# OTEStamperLED.net
KiCad netlist of a schematic drawn in EAGLE
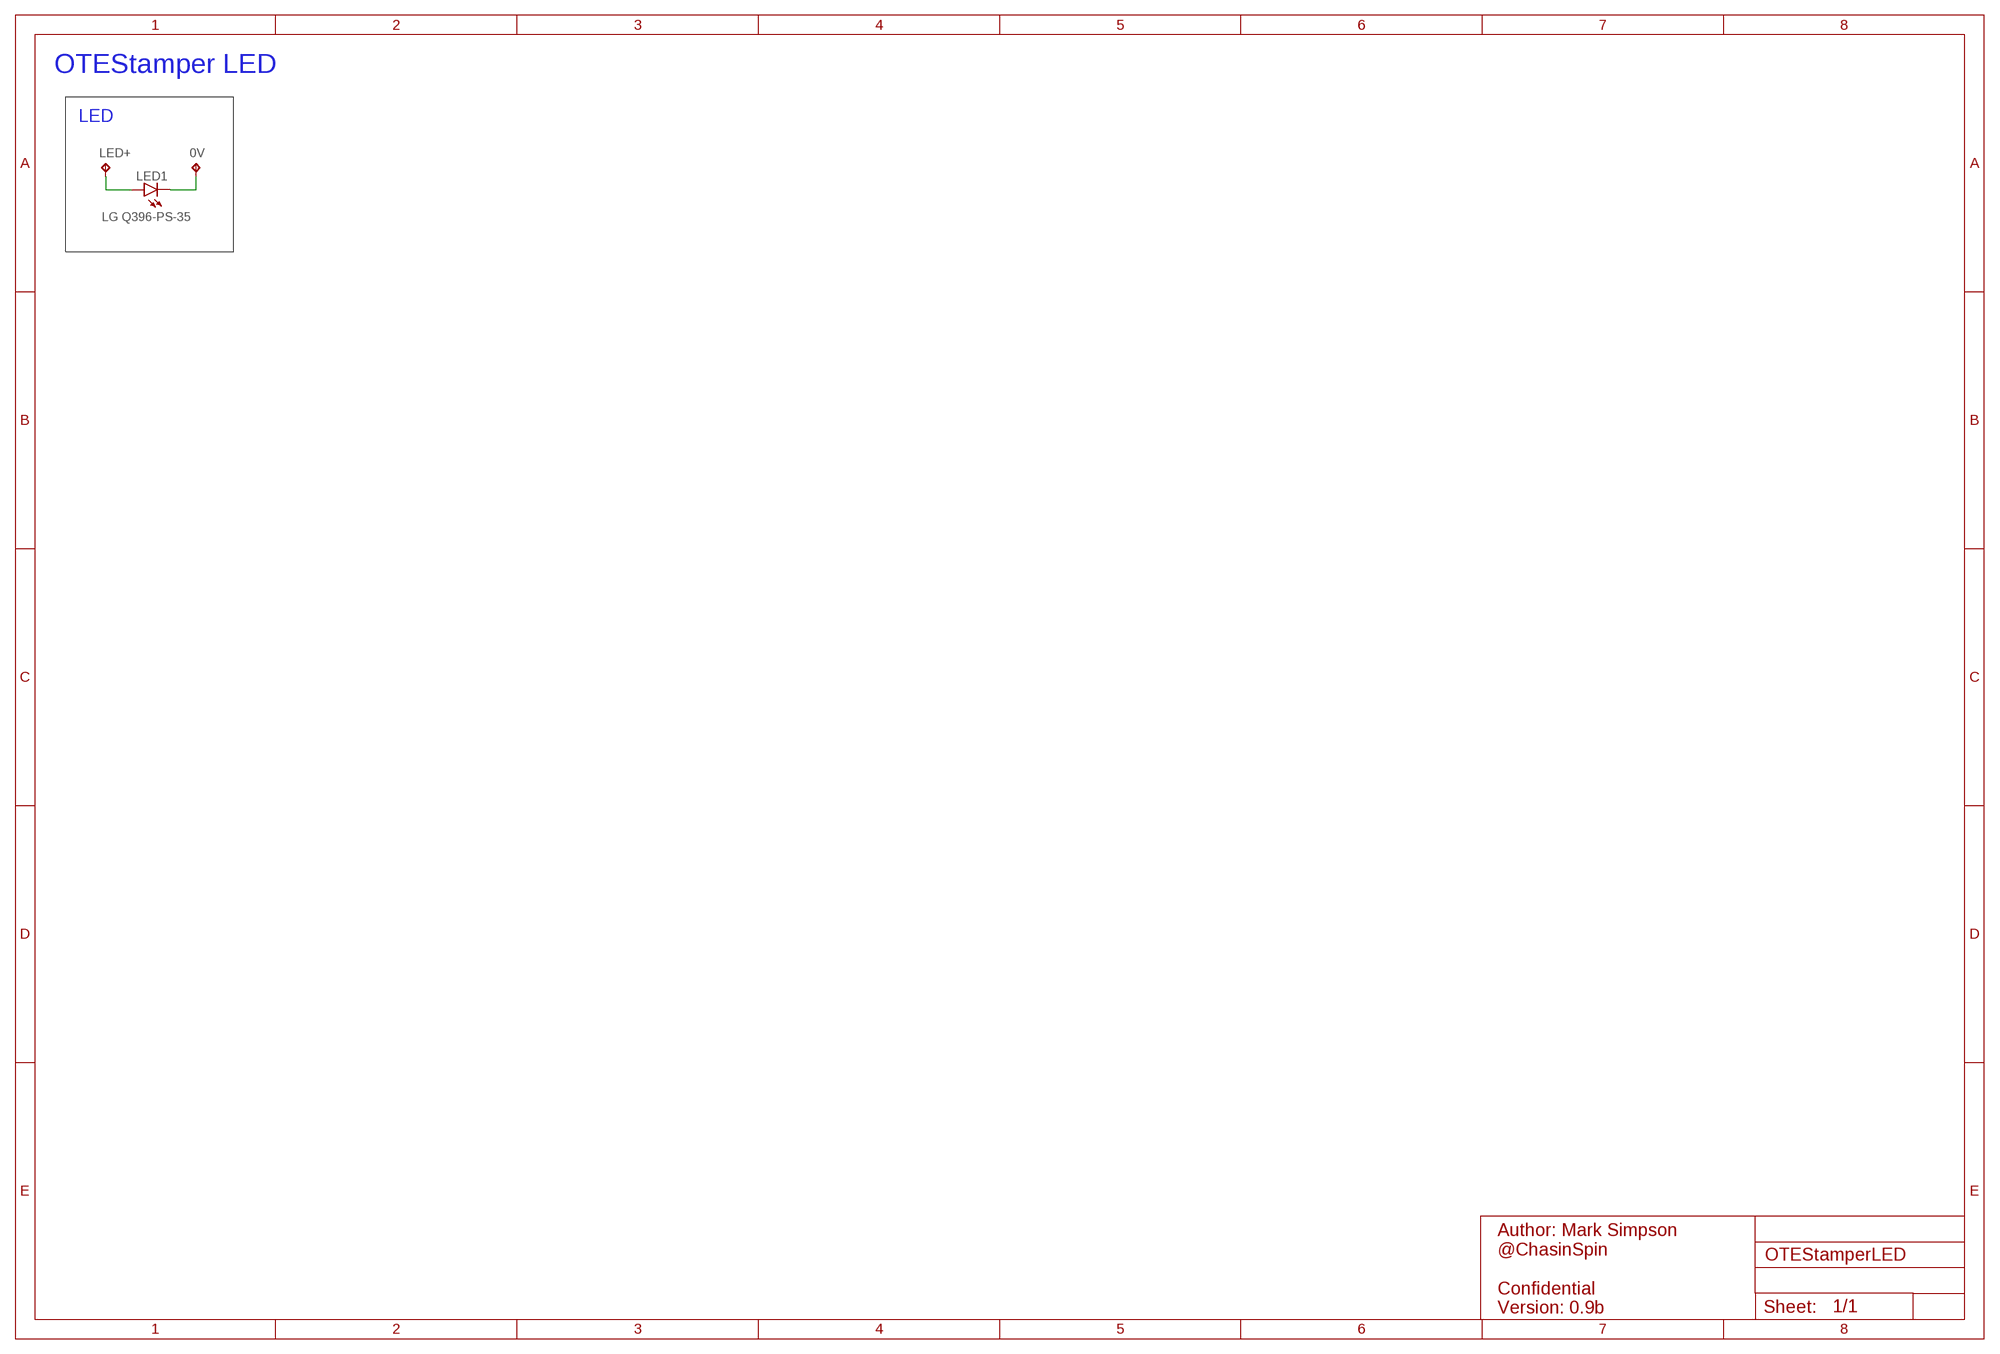
[diagram p0: schematic, sheet 1]

(export (version "E")
  (design (tool "Eeschema 10.0.6"))
  (components
    (comp (ref "0V")
      (value "LED")
      (footprint "eagle-import:TP16SQ")
      (libsource (lib "eagle-import") (part "TPTP16SQ"))
    )
    (comp (ref "LED+")
      (value "LED")
      (footprint "eagle-import:TP16SQ")
      (libsource (lib "eagle-import") (part "TPTP16SQ"))
    )
    (comp (ref "LED1")
      (value "LG Q396-PS-35")
      (footprint "eagle-import:CHIP-LED0603")
      (libsource (lib "eagle-import") (part "LEDCHIP-LED0603"))
    )
  )
  (nets
    (net (code "1") (name "Net-(0V-PadTP)") (class "Default")
      (node (ref "0V") (pin "TP") (pinfunction "TP_TP") (pintype "input"))
      (node (ref "LED1") (pin "C") (pinfunction "C_C") (pintype "passive"))
    )
    (net (code "2") (name "Net-(LED+-PadTP)") (class "Default")
      (node (ref "LED+") (pin "TP") (pinfunction "TP_TP") (pintype "input"))
      (node (ref "LED1") (pin "A") (pinfunction "A_A") (pintype "passive"))
    )
  )
)
